# Qwiic_GPS-RTK_-_ublox_NEO-M8P.net
KiCad netlist of a schematic drawn in EAGLE
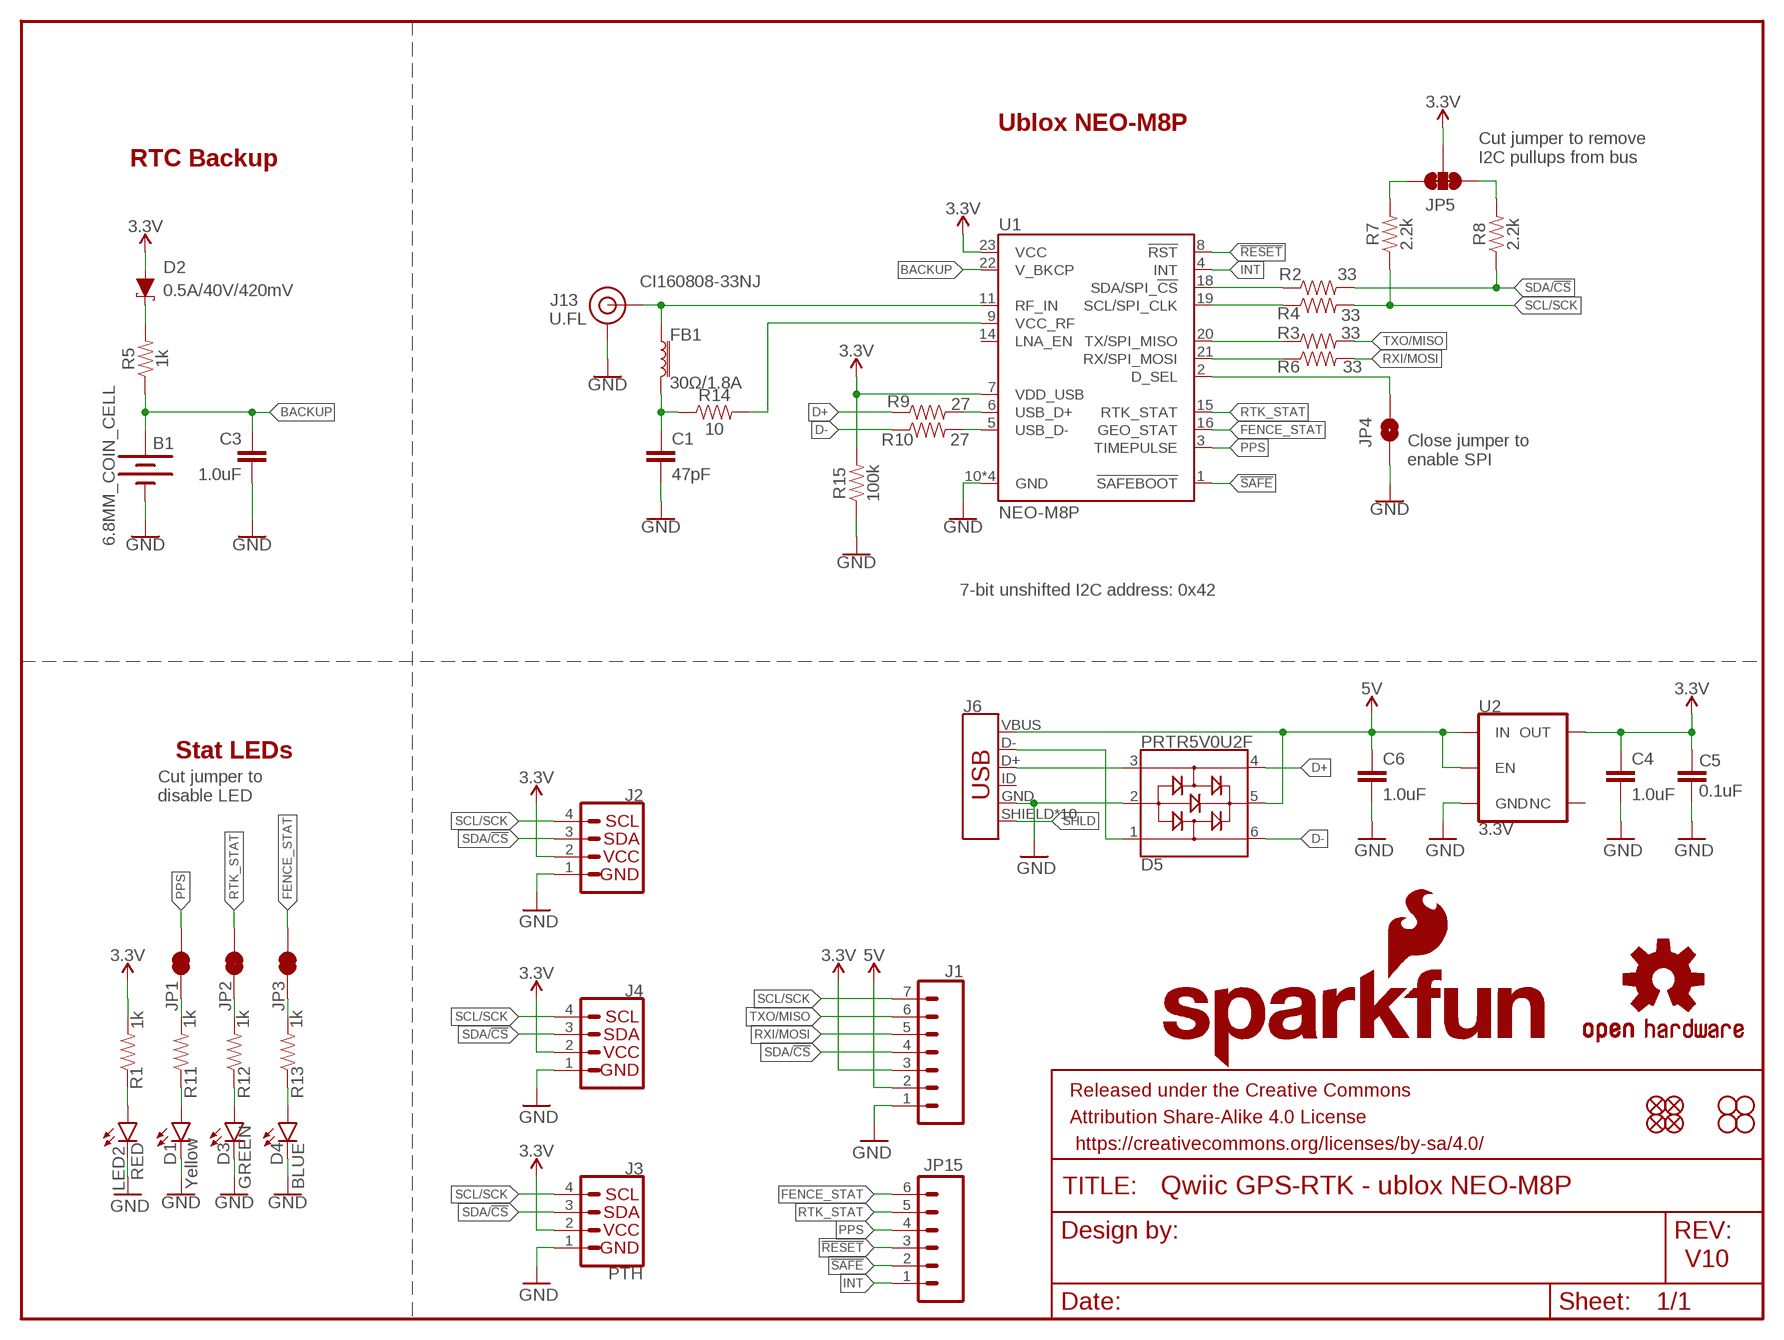
[diagram p0: schematic, sheet 1]

(export (version "E")
  (design (tool "Eeschema 10.0.6"))
  (components
    (comp (ref "B1")
      (value "6.8MM_COIN_CELL")
      (footprint "eagle-import:BATTCON-6.8MM")
      (libsource (lib "eagle-import") (part "BATTERY-6.8MM_SMD"))
    )
    (comp (ref "C1")
      (value "47pF")
      (footprint "eagle-import:0603")
      (libsource (lib "eagle-import") (part "47PF-0603-50V-5%"))
    )
    (comp (ref "C3")
      (value "1.0uF")
      (footprint "eagle-import:0603")
      (libsource (lib "eagle-import") (part "1.0UF-0603-16V-10%"))
    )
    (comp (ref "C4")
      (value "1.0uF")
      (footprint "eagle-import:0603")
      (libsource (lib "eagle-import") (part "1.0UF-0603-16V-10%"))
    )
    (comp (ref "C5")
      (value "0.1uF")
      (footprint "eagle-import:0603")
      (libsource (lib "eagle-import") (part "0.1UF-0603-25V-(+80/-20%)"))
    )
    (comp (ref "C6")
      (value "1.0uF")
      (footprint "eagle-import:0603")
      (libsource (lib "eagle-import") (part "1.0UF-0603-16V-10%"))
    )
    (comp (ref "D1")
      (value "Yellow")
      (footprint "eagle-import:LED-0603")
      (libsource (lib "eagle-import") (part "LED-YELLOW0603"))
    )
    (comp (ref "D2")
      (value "0.5A/40V/420mV")
      (footprint "eagle-import:SOD-323")
      (libsource (lib "eagle-import") (part "DIODE-SCHOTTKY-PMEG4005EJ"))
    )
    (comp (ref "D3")
      (value "GREEN")
      (footprint "eagle-import:LED-0603")
      (libsource (lib "eagle-import") (part "LED-GREEN0603"))
    )
    (comp (ref "D4")
      (value "BLUE")
      (footprint "eagle-import:LED-0603")
      (libsource (lib "eagle-import") (part "LED-BLUE0603"))
    )
    (comp (ref "D5")
      (value "PRTR5V0U2F")
      (footprint "eagle-import:SOT886")
      (libsource (lib "eagle-import") (part "PRTR5V0U2F"))
    )
    (comp (ref "FB1")
      (value "30Ω/1.8A")
      (footprint "eagle-import:0603")
      (libsource (lib "eagle-import") (part "FERRITE_BEAD-0603"))
    )
    (comp (ref "FRAME1")
      (value "FRAME-LETTER")
      (footprint "eagle-import:CREATIVE_COMMONS")
      (libsource (lib "eagle-import") (part "FRAME-LETTER"))
    )
    (comp (ref "J1")
      (value "CONN_07NO_SILK")
      (footprint "eagle-import:1X07_NO_SILK")
      (libsource (lib "eagle-import") (part "CONN_07NO_SILK"))
    )
    (comp (ref "J2")
      (value "I2C_STANDARDQWIIC")
      (footprint "eagle-import:1X04_1MM_RA")
      (libsource (lib "eagle-import") (part "I2C_STANDARDQWIIC"))
    )
    (comp (ref "J3")
      (value "PTH")
      (footprint "eagle-import:1X04_NO_SILK")
      (libsource (lib "eagle-import") (part "SparkX_I2C_STANDARD_NO_SILK"))
    )
    (comp (ref "J4")
      (value "I2C_STANDARDQWIIC")
      (footprint "eagle-import:1X04_1MM_RA")
      (libsource (lib "eagle-import") (part "I2C_STANDARDQWIIC"))
    )
    (comp (ref "J6")
      (value "USB_MICRO-B_HALF_PTH_MILL")
      (footprint "eagle-import:USB-MICROB-PTH-MILL")
      (libsource (lib "eagle-import") (part "USB_MICRO-B_HALF_PTH_MILL"))
    )
    (comp (ref "J13")
      (value "U.FL")
      (footprint "eagle-import:U.FL")
      (libsource (lib "eagle-import") (part "U.FL2PIN"))
    )
    (comp (ref "JP1")
      (value "JUMPER-SMT_2_NC_TRACE_SILK")
      (footprint "eagle-import:SMT-JUMPER_2_NC_TRACE_SILK")
      (libsource (lib "eagle-import") (part "JUMPER-SMT_2_NC_TRACE_SILK"))
    )
    (comp (ref "JP2")
      (value "JUMPER-SMT_2_NC_TRACE_SILK")
      (footprint "eagle-import:SMT-JUMPER_2_NC_TRACE_SILK")
      (libsource (lib "eagle-import") (part "JUMPER-SMT_2_NC_TRACE_SILK"))
    )
    (comp (ref "JP3")
      (value "JUMPER-SMT_2_NC_TRACE_SILK")
      (footprint "eagle-import:SMT-JUMPER_2_NC_TRACE_SILK")
      (libsource (lib "eagle-import") (part "JUMPER-SMT_2_NC_TRACE_SILK"))
    )
    (comp (ref "JP4")
      (value "JUMPER-SMT_2_NO_SILK")
      (footprint "eagle-import:SMT-JUMPER_2_NO_SILK")
      (libsource (lib "eagle-import") (part "JUMPER-SMT_2_NO_SILK"))
    )
    (comp (ref "JP5")
      (value "JUMPER-SMT_3_2-NC_TRACE_SILK")
      (footprint "eagle-import:SMT-JUMPER_3_2-NC_TRACE_SILK")
      (libsource (lib "eagle-import") (part "JUMPER-SMT_3_2-NC_TRACE_SILK"))
    )
    (comp (ref "JP15")
      (value "M06NO_SILK_FEMALE_PTH")
      (footprint "eagle-import:1X06_NO_SILK")
      (libsource (lib "eagle-import") (part "M06NO_SILK_FEMALE_PTH"))
    )
    (comp (ref "JP21")
      (value "FIDUCIALUFIDUCIAL")
      (footprint "eagle-import:MICRO-FIDUCIAL")
      (libsource (lib "eagle-import") (part "FIDUCIALUFIDUCIAL"))
    )
    (comp (ref "JP31")
      (value "STAND-OFF")
      (footprint "eagle-import:STAND-OFF")
      (libsource (lib "eagle-import") (part "STAND-OFF"))
    )
    (comp (ref "JP41")
      (value "STAND-OFF")
      (footprint "eagle-import:STAND-OFF")
      (libsource (lib "eagle-import") (part "STAND-OFF"))
    )
    (comp (ref "JP61")
      (value "FIDUCIALUFIDUCIAL")
      (footprint "eagle-import:MICRO-FIDUCIAL")
      (libsource (lib "eagle-import") (part "FIDUCIALUFIDUCIAL"))
    )
    (comp (ref "JP71")
      (value "FIDUCIALUFIDUCIAL")
      (footprint "eagle-import:MICRO-FIDUCIAL")
      (libsource (lib "eagle-import") (part "FIDUCIALUFIDUCIAL"))
    )
    (comp (ref "JP81")
      (value "FIDUCIALUFIDUCIAL")
      (footprint "eagle-import:MICRO-FIDUCIAL")
      (libsource (lib "eagle-import") (part "FIDUCIALUFIDUCIAL"))
    )
    (comp (ref "JP91")
      (value "STAND-OFF")
      (footprint "eagle-import:STAND-OFF")
      (libsource (lib "eagle-import") (part "STAND-OFF"))
    )
    (comp (ref "JP101")
      (value "STAND-OFF")
      (footprint "eagle-import:STAND-OFF")
      (libsource (lib "eagle-import") (part "STAND-OFF"))
    )
    (comp (ref "LED2")
      (value "RED")
      (footprint "eagle-import:LED-0603")
      (libsource (lib "eagle-import") (part "LED-RED0603"))
    )
    (comp (ref "LOGO1")
      (value "OSHW-LOGOMINI")
      (footprint "eagle-import:OSHW-LOGO-MINI")
      (libsource (lib "eagle-import") (part "OSHW-LOGOMINI"))
    )
    (comp (ref "LOGO2")
      (value "SFE_LOGO_NAME_FLAME.1_INCH")
      (footprint "eagle-import:SFE_LOGO_NAME_FLAME_.1")
      (libsource (lib "eagle-import") (part "SFE_LOGO_NAME_FLAME.1_INCH"))
    )
    (comp (ref "R1")
      (value "1k")
      (footprint "eagle-import:0603")
      (libsource (lib "eagle-import") (part "1KOHM-0603-1/10W-1%"))
    )
    (comp (ref "R2")
      (value "33")
      (footprint "eagle-import:0603")
      (libsource (lib "eagle-import") (part "33OHM-0603-1/10W-1%"))
    )
    (comp (ref "R3")
      (value "33")
      (footprint "eagle-import:0603")
      (libsource (lib "eagle-import") (part "33OHM-0603-1/10W-1%"))
    )
    (comp (ref "R4")
      (value "33")
      (footprint "eagle-import:0603")
      (libsource (lib "eagle-import") (part "33OHM-0603-1/10W-1%"))
    )
    (comp (ref "R5")
      (value "1k")
      (footprint "eagle-import:0603")
      (libsource (lib "eagle-import") (part "1KOHM-0603-1/10W-1%"))
    )
    (comp (ref "R6")
      (value "33")
      (footprint "eagle-import:0603")
      (libsource (lib "eagle-import") (part "33OHM-0603-1/10W-1%"))
    )
    (comp (ref "R7")
      (value "2.2k")
      (footprint "eagle-import:0603")
      (libsource (lib "eagle-import") (part "2.2KOHM-0603-1/10W-1%"))
    )
    (comp (ref "R8")
      (value "2.2k")
      (footprint "eagle-import:0603")
      (libsource (lib "eagle-import") (part "2.2KOHM-0603-1/10W-1%"))
    )
    (comp (ref "R9")
      (value "27")
      (footprint "eagle-import:0603")
      (libsource (lib "eagle-import") (part "27OHM-0603-1/10W-1%"))
    )
    (comp (ref "R10")
      (value "27")
      (footprint "eagle-import:0603")
      (libsource (lib "eagle-import") (part "27OHM-0603-1/10W-1%"))
    )
    (comp (ref "R11")
      (value "1k")
      (footprint "eagle-import:0603")
      (libsource (lib "eagle-import") (part "1KOHM-0603-1/10W-1%"))
    )
    (comp (ref "R12")
      (value "1k")
      (footprint "eagle-import:0603")
      (libsource (lib "eagle-import") (part "1KOHM-0603-1/10W-1%"))
    )
    (comp (ref "R13")
      (value "1k")
      (footprint "eagle-import:0603")
      (libsource (lib "eagle-import") (part "1KOHM-0603-1/10W-1%"))
    )
    (comp (ref "R14")
      (value "10")
      (footprint "eagle-import:0603")
      (libsource (lib "eagle-import") (part "10OHM-0603-1/10W-1%"))
    )
    (comp (ref "R15")
      (value "100k")
      (footprint "eagle-import:0603")
      (libsource (lib "eagle-import") (part "100KOHM-0603-1/10W-1%"))
    )
    (comp (ref "U1")
      (value "NEO-M8P")
      (footprint "eagle-import:NEO-M8P")
      (libsource (lib "eagle-import") (part "NEO-M8PM8P"))
    )
    (comp (ref "U2")
      (value "3.3V")
      (footprint "eagle-import:SOT23-5")
      (libsource (lib "eagle-import") (part "V_REG_AP2112K-3.3V"))
    )
  )
  (nets
    (net (code "1") (name "/SDA{slash}~{CS}") (class "Default")
      (node (ref "J1") (pin "4") (pinfunction "4_4") (pintype "passive"))
      (node (ref "J2") (pin "3") (pinfunction "3_3") (pintype "passive"))
      (node (ref "J3") (pin "3") (pinfunction "SDA_3") (pintype "passive"))
      (node (ref "J4") (pin "3") (pinfunction "3_3") (pintype "passive"))
      (node (ref "R2") (pin "2") (pinfunction "2_2") (pintype "passive"))
      (node (ref "R8") (pin "1") (pinfunction "1_1") (pintype "passive"))
    )
    (net (code "2") (name "/~{RESET}") (class "Default")
      (node (ref "JP15") (pin "3") (pinfunction "3_3") (pintype "passive"))
      (node (ref "U1") (pin "8") (pinfunction "~{RST}_8") (pintype "bidirectional"))
    )
    (net (code "3") (name "/~{SAFE}") (class "Default")
      (node (ref "JP15") (pin "2") (pinfunction "2_2") (pintype "passive"))
      (node (ref "U1") (pin "1") (pinfunction "~{SAFEBOOT}_1") (pintype "bidirectional"))
    )
    (net (code "4") (name "3.3V") (class "Default")
      (node (ref "C4") (pin "1") (pinfunction "1_1") (pintype "passive"))
      (node (ref "C5") (pin "2") (pinfunction "2_2") (pintype "passive"))
      (node (ref "D2") (pin "A") (pinfunction "A_A") (pintype "passive"))
      (node (ref "J1") (pin "3") (pinfunction "3_3") (pintype "passive"))
      (node (ref "J2") (pin "2") (pinfunction "2_2") (pintype "power_in"))
      (node (ref "J3") (pin "2") (pinfunction "VCC_2") (pintype "power_in"))
      (node (ref "J4") (pin "2") (pinfunction "2_2") (pintype "power_in"))
      (node (ref "JP5") (pin "2") (pinfunction "2_2") (pintype "passive"))
      (node (ref "R1") (pin "2") (pinfunction "2_2") (pintype "passive"))
      (node (ref "R15") (pin "2") (pinfunction "2_2") (pintype "passive"))
      (node (ref "U1") (pin "23") (pinfunction "VCC_23") (pintype "bidirectional"))
      (node (ref "U1") (pin "7") (pinfunction "VDD_USB_7") (pintype "bidirectional"))
      (node (ref "U2") (pin "5") (pinfunction "OUT_5") (pintype "passive"))
    )
    (net (code "5") (name "5V") (class "Default")
      (node (ref "C6") (pin "1") (pinfunction "1_1") (pintype "passive"))
      (node (ref "D5") (pin "5") (pinfunction "5_5") (pintype "bidirectional"))
      (node (ref "J1") (pin "2") (pinfunction "2_2") (pintype "passive"))
      (node (ref "J6") (pin "VBUS") (pinfunction "VBUS_VBUS") (pintype "power_in"))
      (node (ref "U2") (pin "1") (pinfunction "IN_1") (pintype "input"))
      (node (ref "U2") (pin "3") (pinfunction "EN_3") (pintype "input"))
    )
    (net (code "6") (name "BACKUP") (class "Default")
      (node (ref "B1") (pin "+") (pinfunction "+_+") (pintype "power_in"))
      (node (ref "C3") (pin "1") (pinfunction "1_1") (pintype "passive"))
      (node (ref "R5") (pin "1") (pinfunction "1_1") (pintype "passive"))
      (node (ref "U1") (pin "22") (pinfunction "V_BKCP_22") (pintype "bidirectional"))
    )
    (net (code "7") (name "D+") (class "Default")
      (node (ref "D5") (pin "4") (pinfunction "4_4") (pintype "bidirectional"))
      (node (ref "R9") (pin "1") (pinfunction "1_1") (pintype "passive"))
    )
    (net (code "8") (name "D-") (class "Default")
      (node (ref "D5") (pin "6") (pinfunction "6_6") (pintype "bidirectional"))
      (node (ref "R10") (pin "1") (pinfunction "1_1") (pintype "passive"))
    )
    (net (code "9") (name "FENCE_STAT") (class "Default")
      (node (ref "JP15") (pin "6") (pinfunction "6_6") (pintype "passive"))
      (node (ref "JP3") (pin "2") (pinfunction "2_2") (pintype "passive"))
      (node (ref "U1") (pin "16") (pinfunction "GEO_STAT_16") (pintype "bidirectional"))
    )
    (net (code "10") (name "GND") (class "Default")
      (node (ref "B1") (pin "-") (pinfunction "-_-") (pintype "power_in"))
      (node (ref "C1") (pin "2") (pinfunction "2_2") (pintype "passive"))
      (node (ref "C3") (pin "2") (pinfunction "2_2") (pintype "passive"))
      (node (ref "C4") (pin "2") (pinfunction "2_2") (pintype "passive"))
      (node (ref "C5") (pin "1") (pinfunction "1_1") (pintype "passive"))
      (node (ref "C6") (pin "2") (pinfunction "2_2") (pintype "passive"))
      (node (ref "D1") (pin "C") (pinfunction "C_C") (pintype "passive"))
      (node (ref "D3") (pin "C") (pinfunction "C_C") (pintype "passive"))
      (node (ref "D4") (pin "C") (pinfunction "C_C") (pintype "passive"))
      (node (ref "D5") (pin "2") (pinfunction "2_2") (pintype "bidirectional"))
      (node (ref "J1") (pin "1") (pinfunction "1_1") (pintype "passive"))
      (node (ref "J13") (pin "1") (pinfunction "GND_1") (pintype "bidirectional"))
      (node (ref "J13") (pin "2") (pinfunction "GND_2") (pintype "bidirectional"))
      (node (ref "J2") (pin "1") (pinfunction "1_1") (pintype "power_in"))
      (node (ref "J3") (pin "1") (pinfunction "GND_1") (pintype "power_in"))
      (node (ref "J4") (pin "1") (pinfunction "1_1") (pintype "power_in"))
      (node (ref "J6") (pin "GND") (pinfunction "GND_GND") (pintype "power_in"))
      (node (ref "JP4") (pin "1") (pinfunction "1_1") (pintype "passive"))
      (node (ref "LED2") (pin "C") (pinfunction "C_C") (pintype "passive"))
      (node (ref "R15") (pin "1") (pinfunction "1_1") (pintype "passive"))
      (node (ref "U1") (pin "10") (pinfunction "GND_10") (pintype "bidirectional"))
      (node (ref "U1") (pin "12") (pinfunction "GND_12") (pintype "bidirectional"))
      (node (ref "U1") (pin "13") (pinfunction "GND_13") (pintype "bidirectional"))
      (node (ref "U1") (pin "24") (pinfunction "GND_24") (pintype "bidirectional"))
      (node (ref "U2") (pin "2") (pinfunction "GND_2") (pintype "input"))
    )
    (net (code "11") (name "INT") (class "Default")
      (node (ref "JP15") (pin "1") (pinfunction "1_1") (pintype "passive"))
      (node (ref "U1") (pin "4") (pinfunction "INT_4") (pintype "bidirectional"))
    )
    (net (code "12") (name "Net-(C1-Pad1)") (class "Default")
      (node (ref "C1") (pin "1") (pinfunction "1_1") (pintype "passive"))
      (node (ref "FB1") (pin "2") (pinfunction "2_2") (pintype "passive"))
      (node (ref "R14") (pin "1") (pinfunction "1_1") (pintype "passive"))
    )
    (net (code "13") (name "Net-(D1-PadA)") (class "Default")
      (node (ref "D1") (pin "A") (pinfunction "A_A") (pintype "passive"))
      (node (ref "R11") (pin "1") (pinfunction "1_1") (pintype "passive"))
    )
    (net (code "14") (name "Net-(D2-PadC)") (class "Default")
      (node (ref "D2") (pin "C") (pinfunction "C_C") (pintype "passive"))
      (node (ref "R5") (pin "2") (pinfunction "2_2") (pintype "passive"))
    )
    (net (code "15") (name "Net-(D3-PadA)") (class "Default")
      (node (ref "D3") (pin "A") (pinfunction "A_A") (pintype "passive"))
      (node (ref "R12") (pin "1") (pinfunction "1_1") (pintype "passive"))
    )
    (net (code "16") (name "Net-(D4-PadA)") (class "Default")
      (node (ref "D4") (pin "A") (pinfunction "A_A") (pintype "passive"))
      (node (ref "R13") (pin "1") (pinfunction "1_1") (pintype "passive"))
    )
    (net (code "17") (name "Net-(D5-Pad1)") (class "Default")
      (node (ref "D5") (pin "1") (pinfunction "1_1") (pintype "bidirectional"))
      (node (ref "J6") (pin "D-") (pinfunction "D-_D-") (pintype "bidirectional"))
    )
    (net (code "18") (name "Net-(D5-Pad3)") (class "Default")
      (node (ref "D5") (pin "3") (pinfunction "3_3") (pintype "bidirectional"))
      (node (ref "J6") (pin "D+") (pinfunction "D+_D+") (pintype "bidirectional"))
    )
    (net (code "19") (name "Net-(J13-SIGNAL)") (class "Default")
      (node (ref "FB1") (pin "1") (pinfunction "1_1") (pintype "passive"))
      (node (ref "J13") (pin "FEED") (pinfunction "SIGNAL_FEED") (pintype "bidirectional"))
      (node (ref "U1") (pin "11") (pinfunction "RF_IN_11") (pintype "bidirectional"))
    )
    (net (code "20") (name "Net-(JP1-Pad1)") (class "Default")
      (node (ref "JP1") (pin "1") (pinfunction "1_1") (pintype "passive"))
      (node (ref "R11") (pin "2") (pinfunction "2_2") (pintype "passive"))
    )
    (net (code "21") (name "Net-(JP2-Pad1)") (class "Default")
      (node (ref "JP2") (pin "1") (pinfunction "1_1") (pintype "passive"))
      (node (ref "R12") (pin "2") (pinfunction "2_2") (pintype "passive"))
    )
    (net (code "22") (name "Net-(JP3-Pad1)") (class "Default")
      (node (ref "JP3") (pin "1") (pinfunction "1_1") (pintype "passive"))
      (node (ref "R13") (pin "2") (pinfunction "2_2") (pintype "passive"))
    )
    (net (code "23") (name "Net-(JP5-Pad1)") (class "Default")
      (node (ref "JP5") (pin "1") (pinfunction "1_1") (pintype "passive"))
      (node (ref "R8") (pin "2") (pinfunction "2_2") (pintype "passive"))
    )
    (net (code "24") (name "Net-(JP5-Pad3)") (class "Default")
      (node (ref "JP5") (pin "3") (pinfunction "3_3") (pintype "passive"))
      (node (ref "R7") (pin "2") (pinfunction "2_2") (pintype "passive"))
    )
    (net (code "25") (name "Net-(LED2-PadA)") (class "Default")
      (node (ref "LED2") (pin "A") (pinfunction "A_A") (pintype "passive"))
      (node (ref "R1") (pin "1") (pinfunction "1_1") (pintype "passive"))
    )
    (net (code "26") (name "Net-(U1-D_SEL)") (class "Default")
      (node (ref "JP4") (pin "2") (pinfunction "2_2") (pintype "passive"))
      (node (ref "U1") (pin "2") (pinfunction "D_SEL_2") (pintype "bidirectional"))
    )
    (net (code "27") (name "Net-(U1-RX{slash}SPI_MOSI)") (class "Default")
      (node (ref "R6") (pin "1") (pinfunction "1_1") (pintype "passive"))
      (node (ref "U1") (pin "21") (pinfunction "RX/SPI_MOSI_21") (pintype "bidirectional"))
    )
    (net (code "28") (name "Net-(U1-SCL{slash}SPI_CLK)") (class "Default")
      (node (ref "R4") (pin "1") (pinfunction "1_1") (pintype "passive"))
      (node (ref "U1") (pin "19") (pinfunction "SCL/SPI_CLK_19") (pintype "bidirectional"))
    )
    (net (code "29") (name "Net-(U1-SDA{slash}SPI_~{CS})") (class "Default")
      (node (ref "R2") (pin "1") (pinfunction "1_1") (pintype "passive"))
      (node (ref "U1") (pin "18") (pinfunction "SDA/SPI_~{CS}_18") (pintype "bidirectional"))
    )
    (net (code "30") (name "Net-(U1-TX{slash}SPI_MISO)") (class "Default")
      (node (ref "R3") (pin "1") (pinfunction "1_1") (pintype "passive"))
      (node (ref "U1") (pin "20") (pinfunction "TX/SPI_MISO_20") (pintype "bidirectional"))
    )
    (net (code "31") (name "Net-(U1-USB_D+)") (class "Default")
      (node (ref "R9") (pin "2") (pinfunction "2_2") (pintype "passive"))
      (node (ref "U1") (pin "6") (pinfunction "USB_D+_6") (pintype "bidirectional"))
    )
    (net (code "32") (name "Net-(U1-USB_D-)") (class "Default")
      (node (ref "R10") (pin "2") (pinfunction "2_2") (pintype "passive"))
      (node (ref "U1") (pin "5") (pinfunction "USB_D-_5") (pintype "bidirectional"))
    )
    (net (code "33") (name "Net-(U1-VCC_RF)") (class "Default")
      (node (ref "R14") (pin "2") (pinfunction "2_2") (pintype "passive"))
      (node (ref "U1") (pin "9") (pinfunction "VCC_RF_9") (pintype "bidirectional"))
    )
    (net (code "34") (name "PPS") (class "Default")
      (node (ref "JP1") (pin "2") (pinfunction "2_2") (pintype "passive"))
      (node (ref "JP15") (pin "4") (pinfunction "4_4") (pintype "passive"))
      (node (ref "U1") (pin "3") (pinfunction "TIMEPULSE_3") (pintype "bidirectional"))
    )
    (net (code "35") (name "RTK_STAT") (class "Default")
      (node (ref "JP15") (pin "5") (pinfunction "5_5") (pintype "passive"))
      (node (ref "JP2") (pin "2") (pinfunction "2_2") (pintype "passive"))
      (node (ref "U1") (pin "15") (pinfunction "RTK_STAT_15") (pintype "bidirectional"))
    )
    (net (code "36") (name "RXI{slash}MOSI") (class "Default")
      (node (ref "J1") (pin "5") (pinfunction "5_5") (pintype "passive"))
      (node (ref "R6") (pin "2") (pinfunction "2_2") (pintype "passive"))
    )
    (net (code "37") (name "SCL{slash}SCK") (class "Default")
      (node (ref "J1") (pin "7") (pinfunction "7_7") (pintype "passive"))
      (node (ref "J2") (pin "4") (pinfunction "4_4") (pintype "passive"))
      (node (ref "J3") (pin "4") (pinfunction "SCL_4") (pintype "passive"))
      (node (ref "J4") (pin "4") (pinfunction "4_4") (pintype "passive"))
      (node (ref "R4") (pin "2") (pinfunction "2_2") (pintype "passive"))
      (node (ref "R7") (pin "1") (pinfunction "1_1") (pintype "passive"))
    )
    (net (code "38") (name "SHLD") (class "Default")
      (node (ref "J6") (pin "SHIELD") (pinfunction "SHIELD_SHIELD") (pintype "bidirectional"))
      (node (ref "J6") (pin "SHIELD10") (pinfunction "SHIELD_SHIELD10") (pintype "bidirectional"))
      (node (ref "J6") (pin "SHIELD2") (pinfunction "SHIELD_SHIELD2") (pintype "bidirectional"))
      (node (ref "J6") (pin "SHIELD3") (pinfunction "SHIELD_SHIELD3") (pintype "bidirectional"))
      (node (ref "J6") (pin "SHIELD4") (pinfunction "SHIELD_SHIELD4") (pintype "bidirectional"))
      (node (ref "J6") (pin "SHIELD5") (pinfunction "SHIELD_SHIELD5") (pintype "bidirectional"))
      (node (ref "J6") (pin "SHIELD6") (pinfunction "SHIELD_SHIELD6") (pintype "bidirectional"))
      (node (ref "J6") (pin "SHIELD7") (pinfunction "SHIELD_SHIELD7") (pintype "bidirectional"))
      (node (ref "J6") (pin "SHIELD8") (pinfunction "SHIELD_SHIELD8") (pintype "bidirectional"))
      (node (ref "J6") (pin "SHIELD9") (pinfunction "SHIELD_SHIELD9") (pintype "bidirectional"))
    )
    (net (code "39") (name "TXO{slash}MISO") (class "Default")
      (node (ref "J1") (pin "6") (pinfunction "6_6") (pintype "passive"))
      (node (ref "R3") (pin "2") (pinfunction "2_2") (pintype "passive"))
    )
    (net (code "40") (name "unconnected-(J6-PadID)") (class "Default")
      (node (ref "J6") (pin "ID") (pinfunction "ID_ID") (pintype "bidirectional"))
    )
    (net (code "41") (name "unconnected-(U1-LNA_EN-Pad14)") (class "Default")
      (node (ref "U1") (pin "14") (pinfunction "LNA_EN_14") (pintype "bidirectional"))
    )
    (net (code "42") (name "unconnected-(U2-NC-Pad4)") (class "Default")
      (node (ref "U2") (pin "4") (pinfunction "NC_4") (pintype "no_connect"))
    )
  )
)
